# usb_isolation.net
KiCad netlist of a schematic drawn in Altium Designer
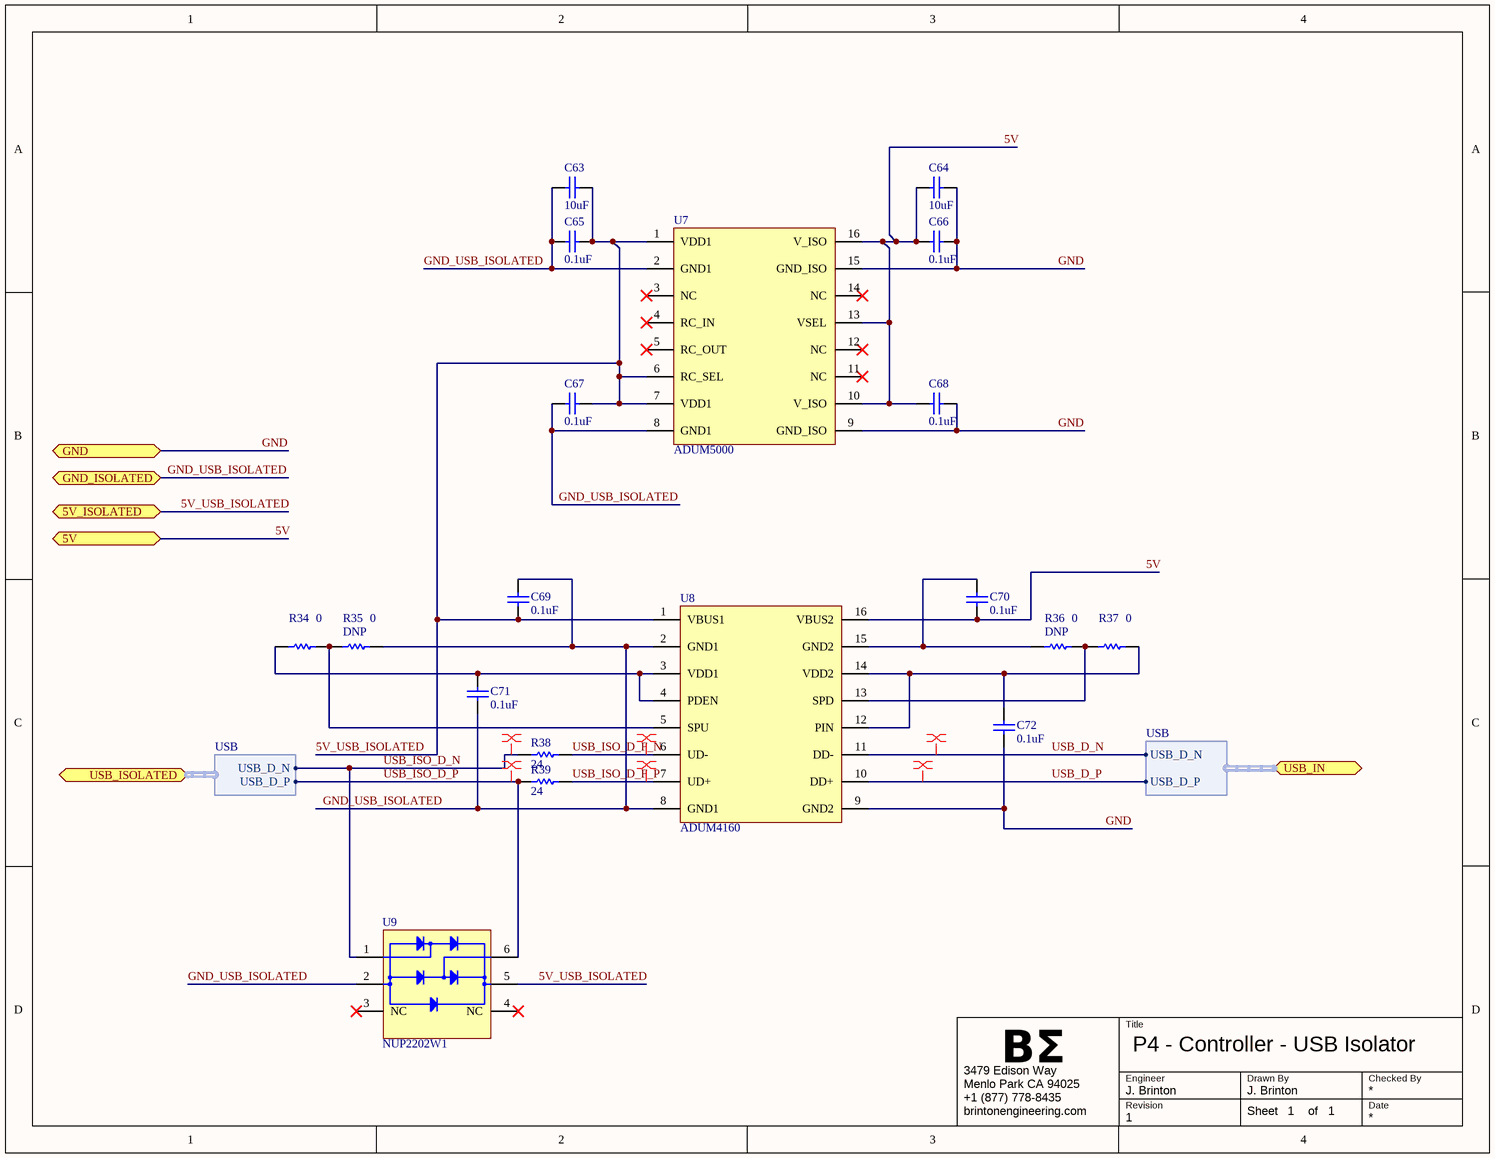
[diagram p0: usb_isolation.SchDoc]

(export (version "E")
  (design (tool "Eeschema 10.0.6"))
  (components
    (comp (ref "C63")
      (value "10uF")
      (footprint "0805")
      (description "Ceramic Capacitor 10uF +/-10% 50V X7S SMD 1210")
      (fields (field (name "MANUFACTURER") "TDK Corporation") (field (name "TOLERANCE") "+/-10%"))
      (libsource (lib "generic") (part "CAP"))
    )
    (comp (ref "C64")
      (value "10uF")
      (footprint "0805")
      (description "Ceramic Capacitor 10uF +/-10% 50V X7S SMD 1210")
      (fields (field (name "MANUFACTURER") "TDK Corporation") (field (name "TOLERANCE") "+/-10%"))
      (libsource (lib "generic") (part "CAP"))
    )
    (comp (ref "C65")
      (value "0.1uF")
      (footprint "0805")
      (description "Ceramic Capacitor 0.1uF +/-10% 50V X7R SMD 0805")
      (fields (field (name "MANUFACTURER") "Murata Electronics") (field (name "TOLERANCE") "+/-10%"))
      (libsource (lib "generic") (part "CAP"))
    )
    (comp (ref "C66")
      (value "0.1uF")
      (footprint "0805")
      (description "Ceramic Capacitor 0.1uF +/-10% 50V X7R SMD 0805")
      (fields (field (name "MANUFACTURER") "Murata Electronics") (field (name "TOLERANCE") "+/-10%"))
      (libsource (lib "generic") (part "CAP"))
    )
    (comp (ref "C67")
      (value "0.1uF")
      (footprint "0805")
      (description "Ceramic Capacitor 0.1uF +/-10% 50V X7R SMD 0805")
      (fields (field (name "MANUFACTURER") "Murata Electronics") (field (name "TOLERANCE") "+/-10%"))
      (libsource (lib "generic") (part "CAP"))
    )
    (comp (ref "C68")
      (value "0.1uF")
      (footprint "0805")
      (description "Ceramic Capacitor 0.1uF +/-10% 50V X7R SMD 0805")
      (fields (field (name "MANUFACTURER") "Murata Electronics") (field (name "TOLERANCE") "+/-10%"))
      (libsource (lib "generic") (part "CAP"))
    )
    (comp (ref "C69")
      (value "0.1uF")
      (footprint "0805")
      (description "Ceramic Capacitor 0.1uF +/-10% 50V X7R SMD 0805")
      (fields (field (name "MANUFACTURER") "Murata Electronics") (field (name "TOLERANCE") "+/-10%"))
      (libsource (lib "generic") (part "CAP"))
    )
    (comp (ref "C70")
      (value "0.1uF")
      (footprint "0805")
      (description "Ceramic Capacitor 0.1uF +/-10% 50V X7R SMD 0805")
      (fields (field (name "MANUFACTURER") "Murata Electronics") (field (name "TOLERANCE") "+/-10%"))
      (libsource (lib "generic") (part "CAP"))
    )
    (comp (ref "C71")
      (value "0.1uF")
      (footprint "0805")
      (description "Ceramic Capacitor 0.1uF +/-10% 50V X7R SMD 0805")
      (fields (field (name "MANUFACTURER") "Murata Electronics") (field (name "TOLERANCE") "+/-10%"))
      (libsource (lib "generic") (part "CAP"))
    )
    (comp (ref "C72")
      (value "0.1uF")
      (footprint "0805")
      (description "Ceramic Capacitor 0.1uF +/-10% 50V X7R SMD 0805")
      (fields (field (name "MANUFACTURER") "Murata Electronics") (field (name "TOLERANCE") "+/-10%"))
      (libsource (lib "generic") (part "CAP"))
    )
    (comp (ref "R34")
      (value "0")
      (footprint "0805")
      (description "Thick Film Chip Resistor 0 Ohms 2A SMD 0805")
      (fields (field (name "MANUFACTURER") "Panasonic - ECG") (field (name "Comment") "RES 0805 0 2A"))
      (libsource (lib "brinton") (part "RES"))
    )
    (comp (ref "R35")
      (value "0")
      (footprint "0805")
      (description "Thick Film Chip Resistor 0 Ohms 2A SMD 0805")
      (fields
        (field (name "MANUFACTURER") "Panasonic - ECG")
        (field (name "DO NOT POPULATE") "DNP")
        (field (name "Comment") "RES 0805 0 2A")
      )
      (libsource (lib "brinton") (part "RES"))
    )
    (comp (ref "R36")
      (value "0")
      (footprint "0805")
      (description "Thick Film Chip Resistor 0 Ohms 2A SMD 0805")
      (fields
        (field (name "MANUFACTURER") "Panasonic - ECG")
        (field (name "DO NOT POPULATE") "DNP")
        (field (name "Comment") "RES 0805 0 2A")
      )
      (libsource (lib "brinton") (part "RES"))
    )
    (comp (ref "R37")
      (value "0")
      (footprint "0805")
      (description "Thick Film Chip Resistor 0 Ohms 2A SMD 0805")
      (fields (field (name "MANUFACTURER") "Panasonic - ECG") (field (name "Comment") "RES 0805 0 2A"))
      (libsource (lib "brinton") (part "RES"))
    )
    (comp (ref "R38")
      (value "24")
      (footprint "0805")
      (description "Thin Film Chip Resistor 24 Ohms +/-0.5% 0.125W 100V SMD 0805")
      (fields (field (name "TOLERANCE") "+/-0.5%") (field (name "MANUFACTURER") "Yageo"))
      (libsource (lib "brinton") (part "RES"))
    )
    (comp (ref "R39")
      (value "24")
      (footprint "0805")
      (description "Thin Film Chip Resistor 24 Ohms +/-0.5% 0.125W 100V SMD 0805")
      (fields (field (name "TOLERANCE") "+/-0.5%") (field (name "MANUFACTURER") "Yageo"))
      (libsource (lib "brinton") (part "RES"))
    )
    (comp (ref "U7")
      (value "ADUM5000")
      (footprint "soic16w_m")
      (description "Isolated DC/DC Converter")
      (fields (field (name "MANUFACTURER") "Analog Devices"))
      (libsource (lib "analog_devices") (part "ADUM5000"))
    )
    (comp (ref "U8")
      (value "ADUM4160")
      (footprint "generic:SOIC16W_M")
      (description "Full/Low Speed 5kV USB Digital Isolator")
      (fields (field (name "MANUFACTURER") "Analog Devices"))
      (libsource (lib "analog_devices") (part "ADUM4160"))
    )
    (comp (ref "U9")
      (value "NUP2202W1")
      (footprint "SOT363")
      (description "Transient Voltage Suppressor")
      (fields (field (name "MANUFACTURER") "On Semiconductor"))
      (libsource (lib "on_semi") (part "NUP2202W1"))
    )
  )
  (nets
    (net (code "2") (name "/5V") (class "Default")
      (node (ref "C64") (pin "1") (pinfunction "1_1") (pintype "passive"))
      (node (ref "C66") (pin "1") (pinfunction "1_1") (pintype "passive"))
      (node (ref "C68") (pin "2") (pinfunction "2_2") (pintype "passive"))
      (node (ref "C70") (pin "1") (pinfunction "1_1") (pintype "passive"))
      (node (ref "U7") (pin "10") (pinfunction "V_ISO_10") (pintype "passive"))
      (node (ref "U7") (pin "13") (pinfunction "VSEL_13") (pintype "passive"))
      (node (ref "U7") (pin "16") (pinfunction "V_ISO_16") (pintype "passive"))
      (node (ref "U8") (pin "16") (pinfunction "VBUS2_16") (pintype "passive"))
    )
    (net (code "3") (name "/5V_USB_ISOLATED") (class "Default")
      (node (ref "C63") (pin "2") (pinfunction "2_2") (pintype "passive"))
      (node (ref "C65") (pin "1") (pinfunction "1_1") (pintype "passive"))
      (node (ref "C67") (pin "1") (pinfunction "1_1") (pintype "passive"))
      (node (ref "C69") (pin "1") (pinfunction "1_1") (pintype "passive"))
      (node (ref "U7") (pin "1") (pinfunction "VDD1_1") (pintype "passive"))
      (node (ref "U7") (pin "6") (pinfunction "RC_SEL_6") (pintype "passive"))
      (node (ref "U7") (pin "7") (pinfunction "VDD1_7") (pintype "passive"))
      (node (ref "U8") (pin "1") (pinfunction "VBUS1_1") (pintype "passive"))
      (node (ref "U9") (pin "5") (pinfunction "VP_5") (pintype "passive"))
    )
    (net (code "4") (name "/GND") (class "Default")
      (node (ref "C64") (pin "2") (pinfunction "2_2") (pintype "passive"))
      (node (ref "C66") (pin "2") (pinfunction "2_2") (pintype "passive"))
      (node (ref "C68") (pin "1") (pinfunction "1_1") (pintype "passive"))
      (node (ref "C72") (pin "1") (pinfunction "1_1") (pintype "passive"))
      (node (ref "U7") (pin "15") (pinfunction "GND_ISO_15") (pintype "passive"))
      (node (ref "U7") (pin "9") (pinfunction "GND_ISO_9") (pintype "passive"))
      (node (ref "U8") (pin "9") (pinfunction "GND2_9") (pintype "passive"))
    )
    (net (code "5") (name "/GND_USB_ISOLATED") (class "Default")
      (node (ref "C63") (pin "1") (pinfunction "1_1") (pintype "passive"))
      (node (ref "C65") (pin "2") (pinfunction "2_2") (pintype "passive"))
      (node (ref "C67") (pin "2") (pinfunction "2_2") (pintype "passive"))
      (node (ref "C69") (pin "2") (pinfunction "2_2") (pintype "passive"))
      (node (ref "C71") (pin "1") (pinfunction "1_1") (pintype "passive"))
      (node (ref "R35") (pin "2") (pinfunction "2_2") (pintype "passive"))
      (node (ref "U7") (pin "2") (pinfunction "GND1_2") (pintype "passive"))
      (node (ref "U7") (pin "8") (pinfunction "GND1_8") (pintype "passive"))
      (node (ref "U8") (pin "2") (pinfunction "GND1_2") (pintype "passive"))
      (node (ref "U8") (pin "8") (pinfunction "GND1_8") (pintype "passive"))
      (node (ref "U9") (pin "2") (pinfunction "VN_2") (pintype "passive"))
    )
    (net (code "6") (name "/USB_D_N") (class "Default")
      (node (ref "U8") (pin "11") (pinfunction "DD-_11") (pintype "passive"))
    )
    (net (code "7") (name "/USB_D_P") (class "Default")
      (node (ref "U8") (pin "10") (pinfunction "DD+_10") (pintype "passive"))
    )
    (net (code "8") (name "/USB_ISO_D_F_N") (class "Default")
      (node (ref "R38") (pin "2") (pinfunction "2_2") (pintype "passive"))
      (node (ref "U8") (pin "6") (pinfunction "UD-_6") (pintype "passive"))
    )
    (net (code "9") (name "/USB_ISO_D_F_P") (class "Default")
      (node (ref "R39") (pin "2") (pinfunction "2_2") (pintype "passive"))
      (node (ref "U8") (pin "7") (pinfunction "UD+_7") (pintype "passive"))
    )
    (net (code "10") (name "/USB_ISO_D_N") (class "Default")
      (node (ref "R38") (pin "1") (pinfunction "1_1") (pintype "passive"))
      (node (ref "U9") (pin "1") (pinfunction "I/O_1") (pintype "passive"))
    )
    (net (code "11") (name "/USB_ISO_D_P") (class "Default")
      (node (ref "R39") (pin "1") (pinfunction "1_1") (pintype "passive"))
      (node (ref "U9") (pin "6") (pinfunction "I/O_6") (pintype "passive"))
    )
    (net (code "13") (name "Net-(C70-Pad2)") (class "Default")
      (node (ref "C70") (pin "2") (pinfunction "2_2") (pintype "passive"))
      (node (ref "R36") (pin "1") (pinfunction "1_1") (pintype "passive"))
      (node (ref "U8") (pin "15") (pinfunction "GND2_15") (pintype "passive"))
    )
    (net (code "14") (name "Net-(U8-PDEN)") (class "Default")
      (node (ref "C71") (pin "2") (pinfunction "2_2") (pintype "passive"))
      (node (ref "R34") (pin "1") (pinfunction "1_1") (pintype "passive"))
      (node (ref "U8") (pin "3") (pinfunction "VDD1_3") (pintype "passive"))
      (node (ref "U8") (pin "4") (pinfunction "PDEN_4") (pintype "passive"))
    )
    (net (code "15") (name "Net-(U8-PIN)") (class "Default")
      (node (ref "C72") (pin "2") (pinfunction "2_2") (pintype "passive"))
      (node (ref "R37") (pin "2") (pinfunction "2_2") (pintype "passive"))
      (node (ref "U8") (pin "12") (pinfunction "PIN_12") (pintype "passive"))
      (node (ref "U8") (pin "14") (pinfunction "VDD2_14") (pintype "passive"))
    )
    (net (code "16") (name "Net-(U8-SPD)") (class "Default")
      (node (ref "R36") (pin "2") (pinfunction "2_2") (pintype "passive"))
      (node (ref "R37") (pin "1") (pinfunction "1_1") (pintype "passive"))
      (node (ref "U8") (pin "13") (pinfunction "SPD_13") (pintype "passive"))
    )
    (net (code "17") (name "Net-(U8-SPU)") (class "Default")
      (node (ref "R34") (pin "2") (pinfunction "2_2") (pintype "passive"))
      (node (ref "R35") (pin "1") (pinfunction "1_1") (pintype "passive"))
      (node (ref "U8") (pin "5") (pinfunction "SPU_5") (pintype "passive"))
    )
    (net (code "18") (name "unconnected-(U7-NC-Pad3)") (class "Default")
      (node (ref "U7") (pin "3") (pinfunction "NC_3") (pintype "passive+no_connect"))
    )
    (net (code "19") (name "unconnected-(U7-NC-Pad11)") (class "Default")
      (node (ref "U7") (pin "11") (pinfunction "NC_11") (pintype "passive+no_connect"))
    )
    (net (code "20") (name "unconnected-(U7-NC-Pad12)") (class "Default")
      (node (ref "U7") (pin "12") (pinfunction "NC_12") (pintype "passive+no_connect"))
    )
    (net (code "21") (name "unconnected-(U7-NC-Pad14)") (class "Default")
      (node (ref "U7") (pin "14") (pinfunction "NC_14") (pintype "passive+no_connect"))
    )
    (net (code "22") (name "unconnected-(U7-RC_IN-Pad4)") (class "Default")
      (node (ref "U7") (pin "4") (pinfunction "RC_IN_4") (pintype "passive+no_connect"))
    )
    (net (code "23") (name "unconnected-(U7-RC_OUT-Pad5)") (class "Default")
      (node (ref "U7") (pin "5") (pinfunction "RC_OUT_5") (pintype "passive+no_connect"))
    )
    (net (code "24") (name "unconnected-(U9-NC-Pad3)") (class "Default")
      (node (ref "U9") (pin "3") (pinfunction "NC_3") (pintype "passive+no_connect"))
    )
    (net (code "25") (name "unconnected-(U9-NC-Pad4)") (class "Default")
      (node (ref "U9") (pin "4") (pinfunction "NC_4") (pintype "passive+no_connect"))
    )
  )
)
